# board.net
KiCad netlist of a schematic drawn in EAGLE
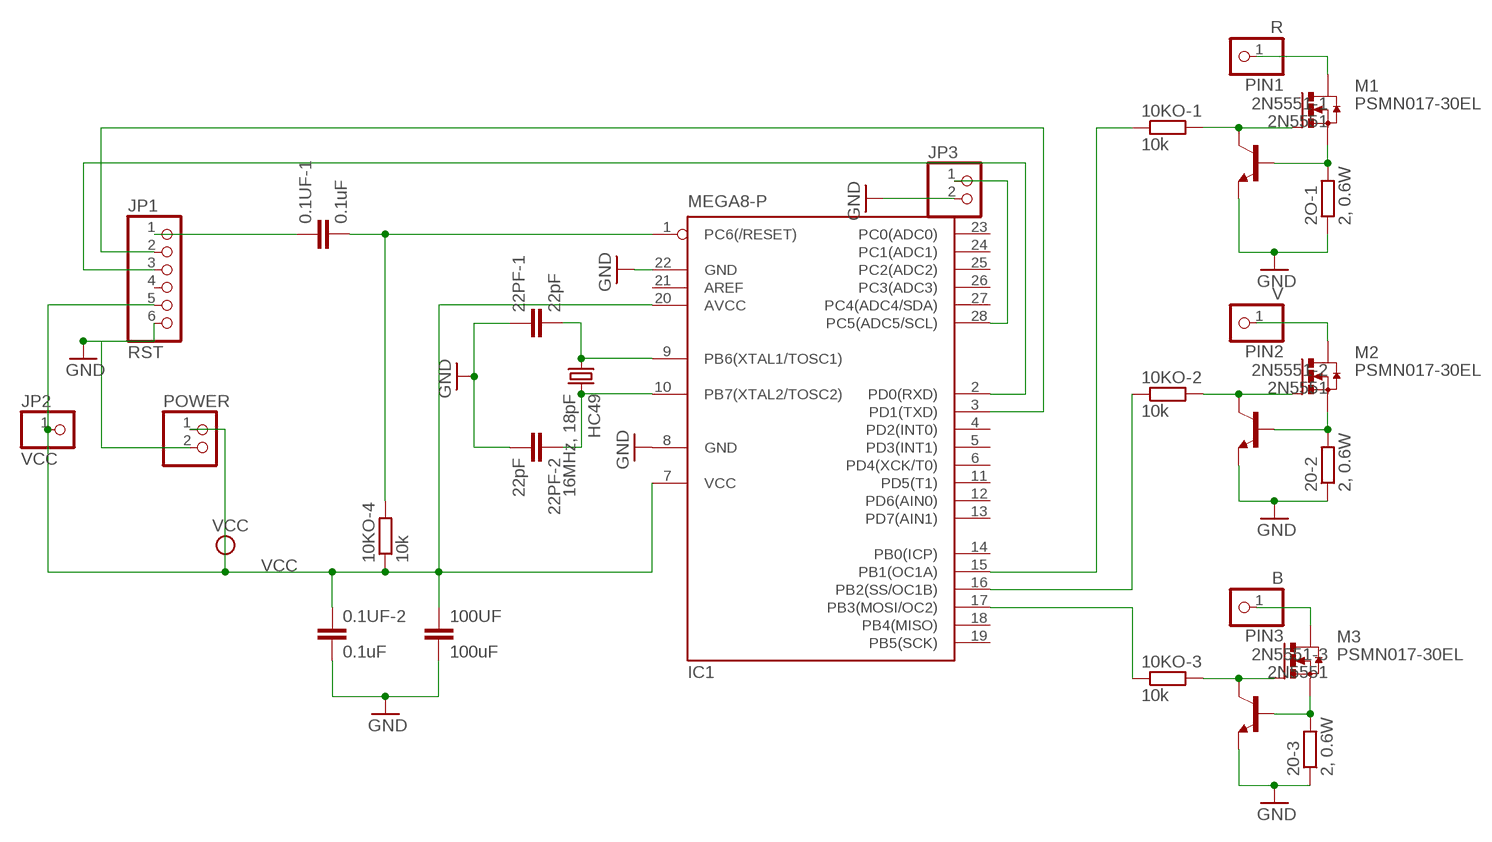
[diagram p0: schematic, sheet 1]

(export (version "E")
  (design (tool "Eeschema 10.0.6"))
  (components
    (comp (ref "0.1UF-1")
      (value "0.1uF")
      (footprint "eagle-import:C025-030X050")
      (libsource (lib "eagle-import") (part "C-EU025-030X050"))
    )
    (comp (ref "0.1UF-2")
      (value "0.1uF")
      (footprint "eagle-import:C025-030X050")
      (libsource (lib "eagle-import") (part "C-EU025-030X050"))
    )
    (comp (ref "2N5551-1")
      (value "2N5551")
      (footprint "eagle-import:TO92-CBE")
      (libsource (lib "eagle-import") (part "-NPN-TO92-CBE2N5551"))
    )
    (comp (ref "2N5551-2")
      (value "2N5551")
      (footprint "eagle-import:TO92-CBE")
      (libsource (lib "eagle-import") (part "-NPN-TO92-CBE2N5551"))
    )
    (comp (ref "2N5551-3")
      (value "2N5551")
      (footprint "eagle-import:TO92-CBE")
      (libsource (lib "eagle-import") (part "-NPN-TO92-CBE2N5551"))
    )
    (comp (ref "2O-1")
      (value "2, 0.6W")
      (footprint "eagle-import:0309V")
      (libsource (lib "eagle-import") (part "R-EU_0309/V"))
    )
    (comp (ref "10KO-1")
      (value "10k")
      (footprint "eagle-import:0207_2V")
      (libsource (lib "eagle-import") (part "R-EU_0207/2V"))
    )
    (comp (ref "10KO-2")
      (value "10k")
      (footprint "eagle-import:0207_2V")
      (libsource (lib "eagle-import") (part "R-EU_0207/2V"))
    )
    (comp (ref "10KO-3")
      (value "10k")
      (footprint "eagle-import:0207_2V")
      (libsource (lib "eagle-import") (part "R-EU_0207/2V"))
    )
    (comp (ref "10KO-4")
      (value "10k")
      (footprint "eagle-import:0207_2V")
      (libsource (lib "eagle-import") (part "R-EU_0207/2V"))
    )
    (comp (ref "20-2")
      (value "2, 0.6W")
      (footprint "eagle-import:0309V")
      (libsource (lib "eagle-import") (part "R-EU_0309/V"))
    )
    (comp (ref "20-3")
      (value "2, 0.6W")
      (footprint "eagle-import:0309V")
      (libsource (lib "eagle-import") (part "R-EU_0309/V"))
    )
    (comp (ref "22PF-1")
      (value "22pF")
      (footprint "eagle-import:C025-030X050")
      (libsource (lib "eagle-import") (part "C-EU025-030X050"))
    )
    (comp (ref "22PF-2")
      (value "22pF")
      (footprint "eagle-import:C025-030X050")
      (libsource (lib "eagle-import") (part "C-EU025-030X050"))
    )
    (comp (ref "100UF")
      (value "100uF")
      (footprint "eagle-import:C025-050X050")
      (libsource (lib "eagle-import") (part "C-EU025-050X050"))
    )
    (comp (ref "HC49")
      (value "16MHz, 18pF")
      (footprint "eagle-import:HC49_S")
      (libsource (lib "eagle-import") (part "CRYSTALHC49S"))
    )
    (comp (ref "IC1")
      (value "MEGA8-P")
      (footprint "eagle-import:DIL28-3")
      (libsource (lib "eagle-import") (part "MEGA8-P"))
    )
    (comp (ref "JP1")
      (value "RST")
      (footprint "eagle-import:1X06")
      (libsource (lib "eagle-import") (part "PINHD-1X6"))
    )
    (comp (ref "JP2")
      (value "VCC")
      (footprint "eagle-import:1X01")
      (libsource (lib "eagle-import") (part "PINHD-1X1"))
    )
    (comp (ref "JP3")
      (value "PINHD-1X2")
      (footprint "eagle-import:1X02")
      (libsource (lib "eagle-import") (part "PINHD-1X2"))
    )
    (comp (ref "M1")
      (value "PSMN017-30EL")
      (footprint "eagle-import:TO262-V")
      (libsource (lib "eagle-import") (part "PSMN017-30ELL-V"))
    )
    (comp (ref "M2")
      (value "PSMN017-30EL")
      (footprint "eagle-import:TO262-V")
      (libsource (lib "eagle-import") (part "PSMN017-30ELL-V"))
    )
    (comp (ref "M3")
      (value "PSMN017-30EL")
      (footprint "eagle-import:TO262-V")
      (libsource (lib "eagle-import") (part "PSMN017-30ELL-V"))
    )
    (comp (ref "PIN1")
      (value "R")
      (footprint "eagle-import:1X01")
      (libsource (lib "eagle-import") (part "PINHD-1X1"))
    )
    (comp (ref "PIN2")
      (value "V")
      (footprint "eagle-import:1X01")
      (libsource (lib "eagle-import") (part "PINHD-1X1"))
    )
    (comp (ref "PIN3")
      (value "B")
      (footprint "eagle-import:1X01")
      (libsource (lib "eagle-import") (part "PINHD-1X1"))
    )
    (comp (ref "POWER")
      (value "PINHD-1X2")
      (footprint "eagle-import:1X02")
      (libsource (lib "eagle-import") (part "PINHD-1X2"))
    )
  )
  (nets
    (net (code "1") (name "GND") (class "Default")
      (node (ref "0.1UF-2") (pin "2") (pinfunction "2_2") (pintype "passive"))
      (node (ref "100UF") (pin "2") (pinfunction "2_2") (pintype "passive"))
      (node (ref "20-2") (pin "1") (pinfunction "1_1") (pintype "passive"))
      (node (ref "20-3") (pin "1") (pinfunction "1_1") (pintype "passive"))
      (node (ref "22PF-1") (pin "1") (pinfunction "1_1") (pintype "passive"))
      (node (ref "22PF-2") (pin "2") (pinfunction "2_2") (pintype "passive"))
      (node (ref "2N5551-1") (pin "E") (pinfunction "E_E") (pintype "passive"))
      (node (ref "2N5551-2") (pin "E") (pinfunction "E_E") (pintype "passive"))
      (node (ref "2N5551-3") (pin "E") (pinfunction "E_E") (pintype "passive"))
      (node (ref "2O-1") (pin "1") (pinfunction "1_1") (pintype "passive"))
      (node (ref "IC1") (pin "22") (pinfunction "GND_22") (pintype "power_in"))
      (node (ref "IC1") (pin "8") (pinfunction "GND_8") (pintype "power_in"))
      (node (ref "JP1") (pin "6") (pinfunction "6_6") (pintype "passive"))
      (node (ref "JP3") (pin "2") (pinfunction "2_2") (pintype "passive"))
      (node (ref "POWER") (pin "2") (pinfunction "2_2") (pintype "passive"))
    )
    (net (code "2") (name "Net-(0.1UF-1-Pad1)") (class "Default")
      (node (ref "0.1UF-1") (pin "1") (pinfunction "1_1") (pintype "passive"))
      (node (ref "JP1") (pin "1") (pinfunction "1_1") (pintype "passive"))
    )
    (net (code "3") (name "Net-(IC1-PB1(OC1A))") (class "Default")
      (node (ref "10KO-1") (pin "1") (pinfunction "1_1") (pintype "passive"))
      (node (ref "IC1") (pin "15") (pinfunction "PB1(OC1A)_15") (pintype "bidirectional"))
    )
    (net (code "4") (name "Net-(IC1-PB2(SS{slash}OC1B))") (class "Default")
      (node (ref "10KO-2") (pin "1") (pinfunction "1_1") (pintype "passive"))
      (node (ref "IC1") (pin "16") (pinfunction "PB2(SS/OC1B)_16") (pintype "bidirectional"))
    )
    (net (code "5") (name "Net-(IC1-PB3(MOSI{slash}OC2))") (class "Default")
      (node (ref "10KO-3") (pin "1") (pinfunction "1_1") (pintype "passive"))
      (node (ref "IC1") (pin "17") (pinfunction "PB3(MOSI/OC2)_17") (pintype "bidirectional"))
    )
    (net (code "6") (name "Net-(IC1-PB6(XTAL1{slash}TOSC1))") (class "Default")
      (node (ref "22PF-1") (pin "2") (pinfunction "2_2") (pintype "passive"))
      (node (ref "HC49") (pin "1") (pinfunction "1_1") (pintype "passive"))
      (node (ref "IC1") (pin "9") (pinfunction "PB6(XTAL1/TOSC1)_9") (pintype "bidirectional"))
    )
    (net (code "7") (name "Net-(IC1-PB7(XTAL2{slash}TOSC2))") (class "Default")
      (node (ref "22PF-2") (pin "1") (pinfunction "1_1") (pintype "passive"))
      (node (ref "HC49") (pin "2") (pinfunction "2_2") (pintype "passive"))
      (node (ref "IC1") (pin "10") (pinfunction "PB7(XTAL2/TOSC2)_10") (pintype "bidirectional"))
    )
    (net (code "8") (name "Net-(IC1-PC5(ADC5{slash}SCL))") (class "Default")
      (node (ref "IC1") (pin "28") (pinfunction "PC5(ADC5/SCL)_28") (pintype "bidirectional"))
      (node (ref "JP3") (pin "1") (pinfunction "1_1") (pintype "passive"))
    )
    (net (code "9") (name "Net-(IC1-PC6({slash}RESET))") (class "Default")
      (node (ref "0.1UF-1") (pin "2") (pinfunction "2_2") (pintype "passive"))
      (node (ref "10KO-4") (pin "2") (pinfunction "2_2") (pintype "passive"))
      (node (ref "IC1") (pin "1") (pinfunction "PC6(/RESET)_1") (pintype "bidirectional"))
    )
    (net (code "10") (name "Net-(IC1-PD0(RXD))") (class "Default")
      (node (ref "IC1") (pin "2") (pinfunction "PD0(RXD)_2") (pintype "bidirectional"))
      (node (ref "JP1") (pin "3") (pinfunction "3_3") (pintype "passive"))
    )
    (net (code "11") (name "Net-(IC1-PD1(TXD))") (class "Default")
      (node (ref "IC1") (pin "3") (pinfunction "PD1(TXD)_3") (pintype "bidirectional"))
      (node (ref "JP1") (pin "2") (pinfunction "2_2") (pintype "passive"))
    )
    (net (code "12") (name "Net-(M1-D)") (class "Default")
      (node (ref "M1") (pin "2") (pinfunction "D_2") (pintype "passive"))
      (node (ref "PIN1") (pin "1") (pinfunction "1_1") (pintype "passive"))
    )
    (net (code "13") (name "Net-(M1-G)") (class "Default")
      (node (ref "10KO-1") (pin "2") (pinfunction "2_2") (pintype "passive"))
      (node (ref "2N5551-1") (pin "C") (pinfunction "C_C") (pintype "passive"))
      (node (ref "M1") (pin "1") (pinfunction "G_1") (pintype "passive"))
    )
    (net (code "14") (name "Net-(M1-S)") (class "Default")
      (node (ref "2N5551-1") (pin "B") (pinfunction "B_B") (pintype "passive"))
      (node (ref "2O-1") (pin "2") (pinfunction "2_2") (pintype "passive"))
      (node (ref "M1") (pin "3") (pinfunction "S_3") (pintype "passive"))
    )
    (net (code "15") (name "Net-(M2-D)") (class "Default")
      (node (ref "M2") (pin "2") (pinfunction "D_2") (pintype "passive"))
      (node (ref "PIN2") (pin "1") (pinfunction "1_1") (pintype "passive"))
    )
    (net (code "16") (name "Net-(M2-G)") (class "Default")
      (node (ref "10KO-2") (pin "2") (pinfunction "2_2") (pintype "passive"))
      (node (ref "2N5551-2") (pin "C") (pinfunction "C_C") (pintype "passive"))
      (node (ref "M2") (pin "1") (pinfunction "G_1") (pintype "passive"))
    )
    (net (code "17") (name "Net-(M2-S)") (class "Default")
      (node (ref "20-2") (pin "2") (pinfunction "2_2") (pintype "passive"))
      (node (ref "2N5551-2") (pin "B") (pinfunction "B_B") (pintype "passive"))
      (node (ref "M2") (pin "3") (pinfunction "S_3") (pintype "passive"))
    )
    (net (code "18") (name "Net-(M3-D)") (class "Default")
      (node (ref "M3") (pin "2") (pinfunction "D_2") (pintype "passive"))
      (node (ref "PIN3") (pin "1") (pinfunction "1_1") (pintype "passive"))
    )
    (net (code "19") (name "Net-(M3-G)") (class "Default")
      (node (ref "10KO-3") (pin "2") (pinfunction "2_2") (pintype "passive"))
      (node (ref "2N5551-3") (pin "C") (pinfunction "C_C") (pintype "passive"))
      (node (ref "M3") (pin "1") (pinfunction "G_1") (pintype "passive"))
    )
    (net (code "20") (name "Net-(M3-S)") (class "Default")
      (node (ref "20-3") (pin "2") (pinfunction "2_2") (pintype "passive"))
      (node (ref "2N5551-3") (pin "B") (pinfunction "B_B") (pintype "passive"))
      (node (ref "M3") (pin "3") (pinfunction "S_3") (pintype "passive"))
    )
    (net (code "21") (name "VCC") (class "Default")
      (node (ref "0.1UF-2") (pin "1") (pinfunction "1_1") (pintype "passive"))
      (node (ref "100UF") (pin "1") (pinfunction "1_1") (pintype "passive"))
      (node (ref "10KO-4") (pin "1") (pinfunction "1_1") (pintype "passive"))
      (node (ref "IC1") (pin "20") (pinfunction "AVCC_20") (pintype "power_in"))
      (node (ref "IC1") (pin "7") (pinfunction "VCC_7") (pintype "power_in"))
      (node (ref "JP1") (pin "5") (pinfunction "5_5") (pintype "passive"))
      (node (ref "JP2") (pin "1") (pinfunction "1_1") (pintype "passive"))
      (node (ref "POWER") (pin "1") (pinfunction "1_1") (pintype "passive"))
    )
    (net (code "22") (name "unconnected-(IC1-AREF-Pad21)") (class "Default")
      (node (ref "IC1") (pin "21") (pinfunction "AREF_21") (pintype "passive"))
    )
    (net (code "23") (name "unconnected-(IC1-PB0(ICP)-Pad14)") (class "Default")
      (node (ref "IC1") (pin "14") (pinfunction "PB0(ICP)_14") (pintype "bidirectional"))
    )
    (net (code "24") (name "unconnected-(IC1-PB4(MISO)-Pad18)") (class "Default")
      (node (ref "IC1") (pin "18") (pinfunction "PB4(MISO)_18") (pintype "bidirectional"))
    )
    (net (code "25") (name "unconnected-(IC1-PB5(SCK)-Pad19)") (class "Default")
      (node (ref "IC1") (pin "19") (pinfunction "PB5(SCK)_19") (pintype "bidirectional"))
    )
    (net (code "26") (name "unconnected-(IC1-PC0(ADC0)-Pad23)") (class "Default")
      (node (ref "IC1") (pin "23") (pinfunction "PC0(ADC0)_23") (pintype "bidirectional"))
    )
    (net (code "27") (name "unconnected-(IC1-PC1(ADC1)-Pad24)") (class "Default")
      (node (ref "IC1") (pin "24") (pinfunction "PC1(ADC1)_24") (pintype "bidirectional"))
    )
    (net (code "28") (name "unconnected-(IC1-PC2(ADC2)-Pad25)") (class "Default")
      (node (ref "IC1") (pin "25") (pinfunction "PC2(ADC2)_25") (pintype "bidirectional"))
    )
    (net (code "29") (name "unconnected-(IC1-PC3(ADC3)-Pad26)") (class "Default")
      (node (ref "IC1") (pin "26") (pinfunction "PC3(ADC3)_26") (pintype "bidirectional"))
    )
    (net (code "30") (name "unconnected-(IC1-PC4(ADC4{slash}SDA)-Pad27)") (class "Default")
      (node (ref "IC1") (pin "27") (pinfunction "PC4(ADC4/SDA)_27") (pintype "bidirectional"))
    )
    (net (code "31") (name "unconnected-(IC1-PD2(INT0)-Pad4)") (class "Default")
      (node (ref "IC1") (pin "4") (pinfunction "PD2(INT0)_4") (pintype "bidirectional"))
    )
    (net (code "32") (name "unconnected-(IC1-PD3(INT1)-Pad5)") (class "Default")
      (node (ref "IC1") (pin "5") (pinfunction "PD3(INT1)_5") (pintype "bidirectional"))
    )
    (net (code "33") (name "unconnected-(IC1-PD4(XCK{slash}T0)-Pad6)") (class "Default")
      (node (ref "IC1") (pin "6") (pinfunction "PD4(XCK/T0)_6") (pintype "bidirectional"))
    )
    (net (code "34") (name "unconnected-(IC1-PD5(T1)-Pad11)") (class "Default")
      (node (ref "IC1") (pin "11") (pinfunction "PD5(T1)_11") (pintype "bidirectional"))
    )
    (net (code "35") (name "unconnected-(IC1-PD6(AIN0)-Pad12)") (class "Default")
      (node (ref "IC1") (pin "12") (pinfunction "PD6(AIN0)_12") (pintype "bidirectional"))
    )
    (net (code "36") (name "unconnected-(IC1-PD7(AIN1)-Pad13)") (class "Default")
      (node (ref "IC1") (pin "13") (pinfunction "PD7(AIN1)_13") (pintype "bidirectional"))
    )
    (net (code "37") (name "unconnected-(JP1-Pad4)") (class "Default")
      (node (ref "JP1") (pin "4") (pinfunction "4_4") (pintype "passive"))
    )
  )
)
